# PressurePoints1X.net
KiCad netlist of a schematic drawn in EAGLE
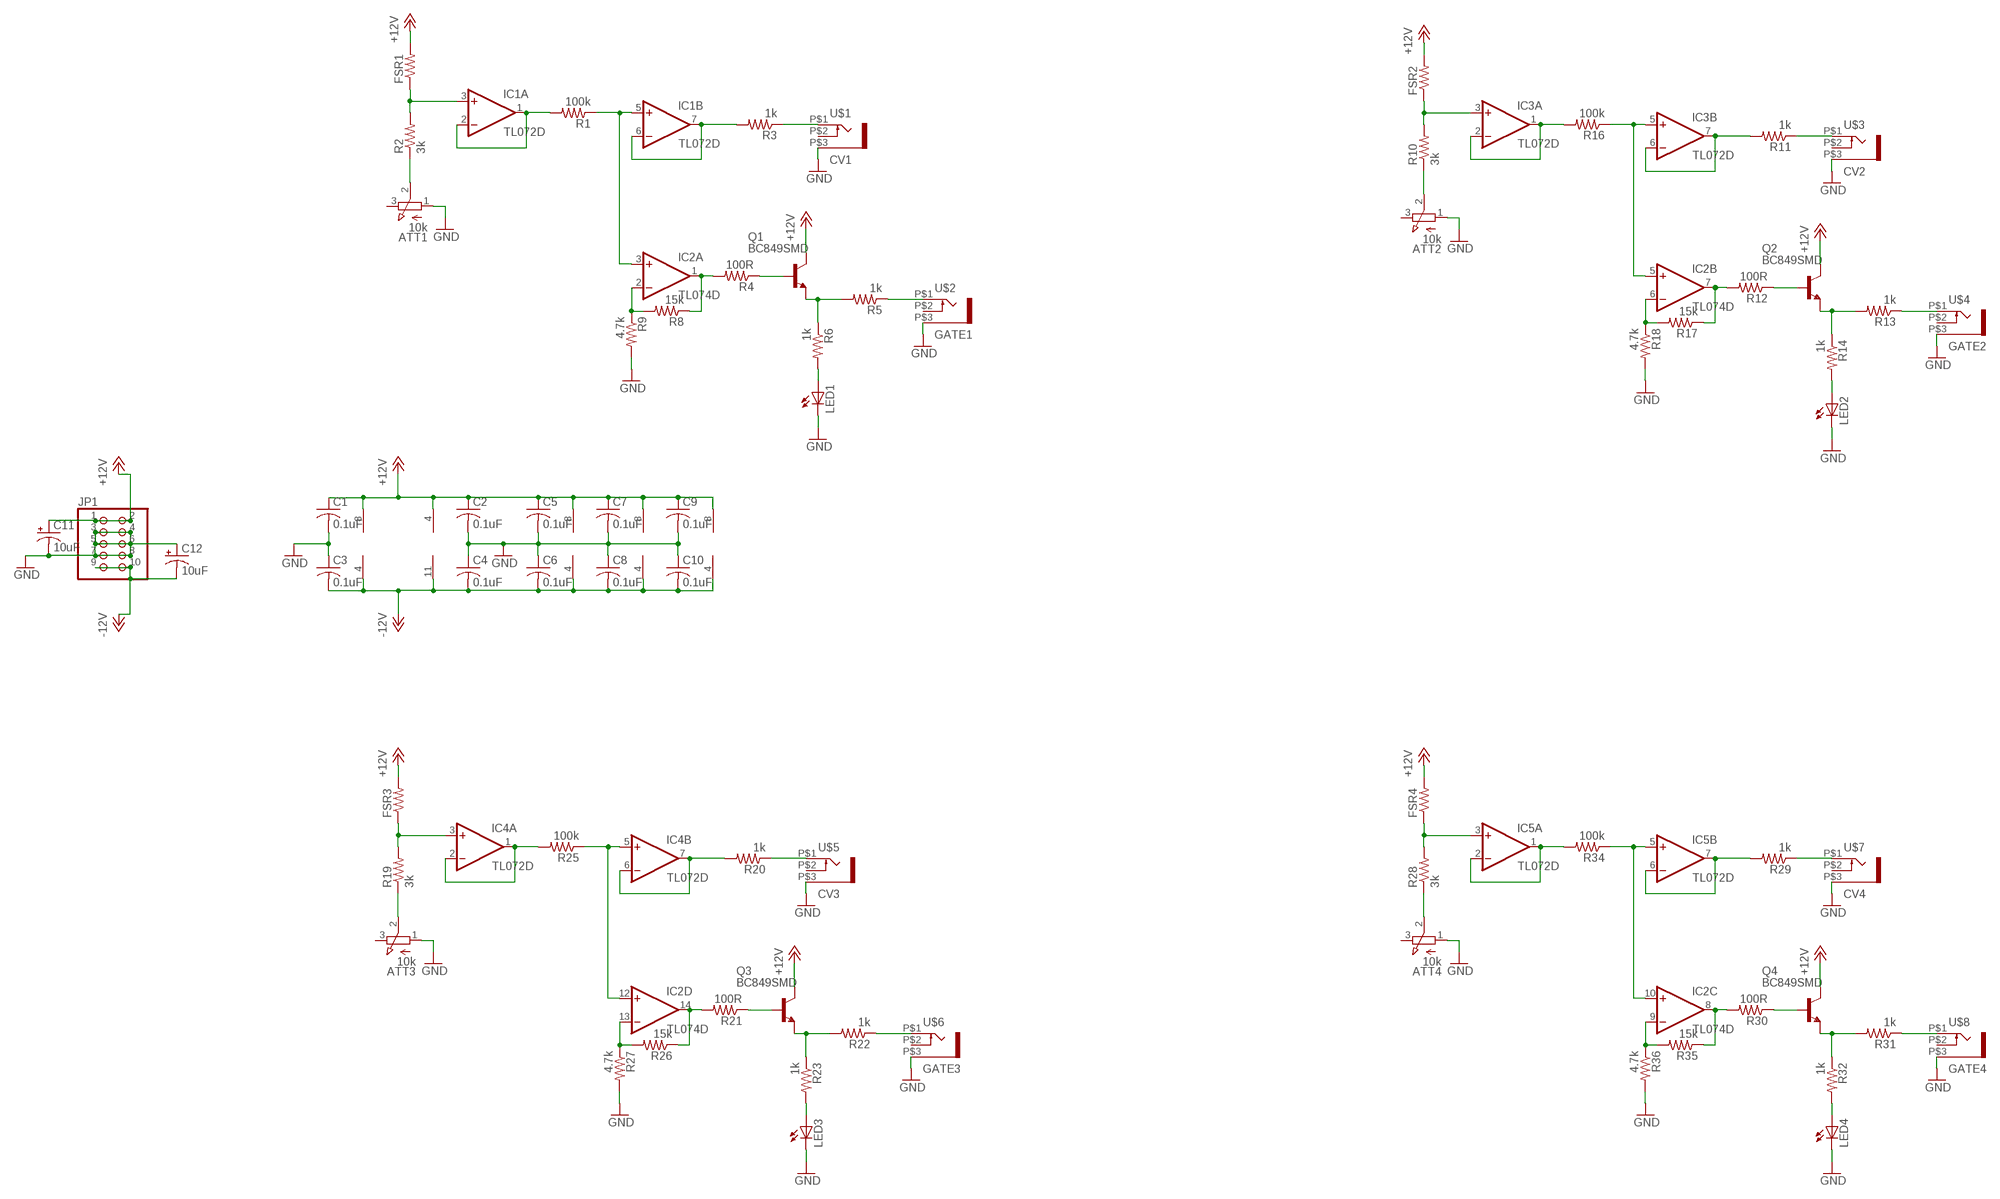
[diagram p0: schematic, sheet 1]

(export (version "E")
  (design (tool "Eeschema 10.0.6"))
  (components
    (comp (ref "ATT1")
      (value "10k")
      (footprint "eagle-import:EVUFXJ")
      (libsource (lib "eagle-import") (part "EVUF2J"))
    )
    (comp (ref "ATT2")
      (value "10k")
      (footprint "eagle-import:EVUFXJ")
      (libsource (lib "eagle-import") (part "EVUF2J"))
    )
    (comp (ref "ATT3")
      (value "10k")
      (footprint "eagle-import:EVUFXJ")
      (libsource (lib "eagle-import") (part "EVUF2J"))
    )
    (comp (ref "ATT4")
      (value "10k")
      (footprint "eagle-import:EVUFXJ")
      (libsource (lib "eagle-import") (part "EVUF2J"))
    )
    (comp (ref "C1")
      (value "0.1uF")
      (footprint "eagle-import:C0603")
      (libsource (lib "eagle-import") (part "C-USC0603"))
    )
    (comp (ref "C2")
      (value "0.1uF")
      (footprint "eagle-import:C0603")
      (libsource (lib "eagle-import") (part "C-USC0603"))
    )
    (comp (ref "C3")
      (value "0.1uF")
      (footprint "eagle-import:C0603")
      (libsource (lib "eagle-import") (part "C-USC0603"))
    )
    (comp (ref "C4")
      (value "0.1uF")
      (footprint "eagle-import:C0603")
      (libsource (lib "eagle-import") (part "C-USC0603"))
    )
    (comp (ref "C5")
      (value "0.1uF")
      (footprint "eagle-import:C0603")
      (libsource (lib "eagle-import") (part "C-USC0603"))
    )
    (comp (ref "C6")
      (value "0.1uF")
      (footprint "eagle-import:C0603")
      (libsource (lib "eagle-import") (part "C-USC0603"))
    )
    (comp (ref "C7")
      (value "0.1uF")
      (footprint "eagle-import:C0603")
      (libsource (lib "eagle-import") (part "C-USC0603"))
    )
    (comp (ref "C8")
      (value "0.1uF")
      (footprint "eagle-import:C0603")
      (libsource (lib "eagle-import") (part "C-USC0603"))
    )
    (comp (ref "C9")
      (value "0.1uF")
      (footprint "eagle-import:C0603")
      (libsource (lib "eagle-import") (part "C-USC0603"))
    )
    (comp (ref "C10")
      (value "0.1uF")
      (footprint "eagle-import:C0603")
      (libsource (lib "eagle-import") (part "C-USC0603"))
    )
    (comp (ref "C11")
      (value "10uF")
      (footprint "eagle-import:E2-5")
      (libsource (lib "eagle-import") (part "CPOL-USE2-5"))
    )
    (comp (ref "C12")
      (value "10uF")
      (footprint "eagle-import:E2-5")
      (libsource (lib "eagle-import") (part "CPOL-USE2-5"))
    )
    (comp (ref "FSR1")
      (value "R-US_0207/2V")
      (footprint "eagle-import:0207_2V")
      (libsource (lib "eagle-import") (part "R-US_0207/2V"))
    )
    (comp (ref "FSR2")
      (value "R-US_0207/2V")
      (footprint "eagle-import:0207_2V")
      (libsource (lib "eagle-import") (part "R-US_0207/2V"))
    )
    (comp (ref "FSR3")
      (value "R-US_0207/2V")
      (footprint "eagle-import:0207_2V")
      (libsource (lib "eagle-import") (part "R-US_0207/2V"))
    )
    (comp (ref "FSR4")
      (value "R-US_0207/2V")
      (footprint "eagle-import:0207_2V")
      (libsource (lib "eagle-import") (part "R-US_0207/2V"))
    )
    (comp (ref "IC1")
      (value "TL072D")
      (footprint "eagle-import:SO08")
      (libsource (lib "eagle-import") (part "TL072D"))
    )
    (comp (ref "IC2")
      (value "TL074D")
      (footprint "eagle-import:SO14")
      (libsource (lib "eagle-import") (part "TL074D"))
    )
    (comp (ref "IC3")
      (value "TL072D")
      (footprint "eagle-import:SO08")
      (libsource (lib "eagle-import") (part "TL072D"))
    )
    (comp (ref "IC4")
      (value "TL072D")
      (footprint "eagle-import:SO08")
      (libsource (lib "eagle-import") (part "TL072D"))
    )
    (comp (ref "IC5")
      (value "TL072D")
      (footprint "eagle-import:SO08")
      (libsource (lib "eagle-import") (part "TL072D"))
    )
    (comp (ref "JP1")
      (value "PINHD-2X5")
      (footprint "eagle-import:2X05")
      (libsource (lib "eagle-import") (part "PINHD-2X5"))
    )
    (comp (ref "LED1")
      (value "LED3MM")
      (footprint "eagle-import:LED3MM")
      (libsource (lib "eagle-import") (part "LED3MM"))
    )
    (comp (ref "LED2")
      (value "LED3MM")
      (footprint "eagle-import:LED3MM")
      (libsource (lib "eagle-import") (part "LED3MM"))
    )
    (comp (ref "LED3")
      (value "LED3MM")
      (footprint "eagle-import:LED3MM")
      (libsource (lib "eagle-import") (part "LED3MM"))
    )
    (comp (ref "LED4")
      (value "LED3MM")
      (footprint "eagle-import:LED3MM")
      (libsource (lib "eagle-import") (part "LED3MM"))
    )
    (comp (ref "Q1")
      (value "BC849SMD")
      (footprint "eagle-import:SOT23-BEC")
      (libsource (lib "eagle-import") (part "BC849SMD"))
    )
    (comp (ref "Q2")
      (value "BC849SMD")
      (footprint "eagle-import:SOT23-BEC")
      (libsource (lib "eagle-import") (part "BC849SMD"))
    )
    (comp (ref "Q3")
      (value "BC849SMD")
      (footprint "eagle-import:SOT23-BEC")
      (libsource (lib "eagle-import") (part "BC849SMD"))
    )
    (comp (ref "Q4")
      (value "BC849SMD")
      (footprint "eagle-import:SOT23-BEC")
      (libsource (lib "eagle-import") (part "BC849SMD"))
    )
    (comp (ref "R1")
      (value "100k")
      (footprint "eagle-import:R0603")
      (libsource (lib "eagle-import") (part "R-US_R0603"))
    )
    (comp (ref "R2")
      (value "3k")
      (footprint "eagle-import:R0603")
      (libsource (lib "eagle-import") (part "R-US_R0603"))
    )
    (comp (ref "R3")
      (value "1k")
      (footprint "eagle-import:R0603")
      (libsource (lib "eagle-import") (part "R-US_R0603"))
    )
    (comp (ref "R4")
      (value "100R")
      (footprint "eagle-import:R0603")
      (libsource (lib "eagle-import") (part "R-US_R0603"))
    )
    (comp (ref "R5")
      (value "1k")
      (footprint "eagle-import:R0603")
      (libsource (lib "eagle-import") (part "R-US_R0603"))
    )
    (comp (ref "R6")
      (value "1k")
      (footprint "eagle-import:R0603")
      (libsource (lib "eagle-import") (part "R-US_R0603"))
    )
    (comp (ref "R8")
      (value "15k")
      (footprint "eagle-import:R0603")
      (libsource (lib "eagle-import") (part "R-US_R0603"))
    )
    (comp (ref "R9")
      (value "4.7k")
      (footprint "eagle-import:R0603")
      (libsource (lib "eagle-import") (part "R-US_R0603"))
    )
    (comp (ref "R10")
      (value "3k")
      (footprint "eagle-import:R0603")
      (libsource (lib "eagle-import") (part "R-US_R0603"))
    )
    (comp (ref "R11")
      (value "1k")
      (footprint "eagle-import:R0603")
      (libsource (lib "eagle-import") (part "R-US_R0603"))
    )
    (comp (ref "R12")
      (value "100R")
      (footprint "eagle-import:R0603")
      (libsource (lib "eagle-import") (part "R-US_R0603"))
    )
    (comp (ref "R13")
      (value "1k")
      (footprint "eagle-import:R0603")
      (libsource (lib "eagle-import") (part "R-US_R0603"))
    )
    (comp (ref "R14")
      (value "1k")
      (footprint "eagle-import:R0603")
      (libsource (lib "eagle-import") (part "R-US_R0603"))
    )
    (comp (ref "R16")
      (value "100k")
      (footprint "eagle-import:R0603")
      (libsource (lib "eagle-import") (part "R-US_R0603"))
    )
    (comp (ref "R17")
      (value "15k")
      (footprint "eagle-import:R0603")
      (libsource (lib "eagle-import") (part "R-US_R0603"))
    )
    (comp (ref "R18")
      (value "4.7k")
      (footprint "eagle-import:R0603")
      (libsource (lib "eagle-import") (part "R-US_R0603"))
    )
    (comp (ref "R19")
      (value "3k")
      (footprint "eagle-import:R0603")
      (libsource (lib "eagle-import") (part "R-US_R0603"))
    )
    (comp (ref "R20")
      (value "1k")
      (footprint "eagle-import:R0603")
      (libsource (lib "eagle-import") (part "R-US_R0603"))
    )
    (comp (ref "R21")
      (value "100R")
      (footprint "eagle-import:R0603")
      (libsource (lib "eagle-import") (part "R-US_R0603"))
    )
    (comp (ref "R22")
      (value "1k")
      (footprint "eagle-import:R0603")
      (libsource (lib "eagle-import") (part "R-US_R0603"))
    )
    (comp (ref "R23")
      (value "1k")
      (footprint "eagle-import:R0603")
      (libsource (lib "eagle-import") (part "R-US_R0603"))
    )
    (comp (ref "R25")
      (value "100k")
      (footprint "eagle-import:R0603")
      (libsource (lib "eagle-import") (part "R-US_R0603"))
    )
    (comp (ref "R26")
      (value "15k")
      (footprint "eagle-import:R0603")
      (libsource (lib "eagle-import") (part "R-US_R0603"))
    )
    (comp (ref "R27")
      (value "4.7k")
      (footprint "eagle-import:R0603")
      (libsource (lib "eagle-import") (part "R-US_R0603"))
    )
    (comp (ref "R28")
      (value "3k")
      (footprint "eagle-import:R0603")
      (libsource (lib "eagle-import") (part "R-US_R0603"))
    )
    (comp (ref "R29")
      (value "1k")
      (footprint "eagle-import:R0603")
      (libsource (lib "eagle-import") (part "R-US_R0603"))
    )
    (comp (ref "R30")
      (value "100R")
      (footprint "eagle-import:R0603")
      (libsource (lib "eagle-import") (part "R-US_R0603"))
    )
    (comp (ref "R31")
      (value "1k")
      (footprint "eagle-import:R0603")
      (libsource (lib "eagle-import") (part "R-US_R0603"))
    )
    (comp (ref "R32")
      (value "1k")
      (footprint "eagle-import:R0603")
      (libsource (lib "eagle-import") (part "R-US_R0603"))
    )
    (comp (ref "R34")
      (value "100k")
      (footprint "eagle-import:R0603")
      (libsource (lib "eagle-import") (part "R-US_R0603"))
    )
    (comp (ref "R35")
      (value "15k")
      (footprint "eagle-import:R0603")
      (libsource (lib "eagle-import") (part "R-US_R0603"))
    )
    (comp (ref "R36")
      (value "4.7k")
      (footprint "eagle-import:R0603")
      (libsource (lib "eagle-import") (part "R-US_R0603"))
    )
    (comp (ref "U$1")
      (value "CV1")
      (footprint "eagle-import:WQP-PJ301M-12_JACK")
      (libsource (lib "eagle-import") (part "WQP-PJ301M-12_JACK"))
    )
    (comp (ref "U$2")
      (value "GATE1")
      (footprint "eagle-import:WQP-PJ301M-12_JACK")
      (libsource (lib "eagle-import") (part "WQP-PJ301M-12_JACK"))
    )
    (comp (ref "U$3")
      (value "CV2")
      (footprint "eagle-import:WQP-PJ301M-12_JACK")
      (libsource (lib "eagle-import") (part "WQP-PJ301M-12_JACK"))
    )
    (comp (ref "U$4")
      (value "GATE2")
      (footprint "eagle-import:WQP-PJ301M-12_JACK")
      (libsource (lib "eagle-import") (part "WQP-PJ301M-12_JACK"))
    )
    (comp (ref "U$5")
      (value "CV3")
      (footprint "eagle-import:WQP-PJ301M-12_JACK")
      (libsource (lib "eagle-import") (part "WQP-PJ301M-12_JACK"))
    )
    (comp (ref "U$6")
      (value "GATE3")
      (footprint "eagle-import:WQP-PJ301M-12_JACK")
      (libsource (lib "eagle-import") (part "WQP-PJ301M-12_JACK"))
    )
    (comp (ref "U$7")
      (value "CV4")
      (footprint "eagle-import:WQP-PJ301M-12_JACK")
      (libsource (lib "eagle-import") (part "WQP-PJ301M-12_JACK"))
    )
    (comp (ref "U$8")
      (value "GATE4")
      (footprint "eagle-import:WQP-PJ301M-12_JACK")
      (libsource (lib "eagle-import") (part "WQP-PJ301M-12_JACK"))
    )
  )
  (nets
    (net (code "1") (name "+12V") (class "Default")
      (node (ref "C1") (pin "1") (pinfunction "1_1") (pintype "passive"))
      (node (ref "C11") (pin "+") (pinfunction "+_+") (pintype "passive"))
      (node (ref "C2") (pin "1") (pinfunction "1_1") (pintype "passive"))
      (node (ref "C5") (pin "1") (pinfunction "1_1") (pintype "passive"))
      (node (ref "C7") (pin "1") (pinfunction "1_1") (pintype "passive"))
      (node (ref "C9") (pin "1") (pinfunction "1_1") (pintype "passive"))
      (node (ref "FSR1") (pin "2") (pinfunction "2_2") (pintype "passive"))
      (node (ref "FSR2") (pin "2") (pinfunction "2_2") (pintype "passive"))
      (node (ref "FSR3") (pin "2") (pinfunction "2_2") (pintype "passive"))
      (node (ref "FSR4") (pin "2") (pinfunction "2_2") (pintype "passive"))
      (node (ref "IC1") (pin "8") (pinfunction "V+_8") (pintype "power_in"))
      (node (ref "IC2") (pin "4") (pinfunction "V+_4") (pintype "power_in"))
      (node (ref "IC3") (pin "8") (pinfunction "V+_8") (pintype "power_in"))
      (node (ref "IC4") (pin "8") (pinfunction "V+_8") (pintype "power_in"))
      (node (ref "IC5") (pin "8") (pinfunction "V+_8") (pintype "power_in"))
      (node (ref "JP1") (pin "1") (pinfunction "1_1") (pintype "passive"))
      (node (ref "JP1") (pin "2") (pinfunction "2_2") (pintype "passive"))
      (node (ref "Q1") (pin "C") (pinfunction "C_C") (pintype "passive"))
      (node (ref "Q2") (pin "C") (pinfunction "C_C") (pintype "passive"))
      (node (ref "Q3") (pin "C") (pinfunction "C_C") (pintype "passive"))
      (node (ref "Q4") (pin "C") (pinfunction "C_C") (pintype "passive"))
    )
    (net (code "2") (name "-12V") (class "Default")
      (node (ref "C10") (pin "2") (pinfunction "2_2") (pintype "passive"))
      (node (ref "C12") (pin "-") (pinfunction "-_-") (pintype "passive"))
      (node (ref "C3") (pin "2") (pinfunction "2_2") (pintype "passive"))
      (node (ref "C4") (pin "2") (pinfunction "2_2") (pintype "passive"))
      (node (ref "C6") (pin "2") (pinfunction "2_2") (pintype "passive"))
      (node (ref "C8") (pin "2") (pinfunction "2_2") (pintype "passive"))
      (node (ref "IC1") (pin "4") (pinfunction "V-_4") (pintype "power_in"))
      (node (ref "IC2") (pin "11") (pinfunction "V-_11") (pintype "power_in"))
      (node (ref "IC3") (pin "4") (pinfunction "V-_4") (pintype "power_in"))
      (node (ref "IC4") (pin "4") (pinfunction "V-_4") (pintype "power_in"))
      (node (ref "IC5") (pin "4") (pinfunction "V-_4") (pintype "power_in"))
      (node (ref "JP1") (pin "10") (pinfunction "10_10") (pintype "passive"))
      (node (ref "JP1") (pin "9") (pinfunction "9_9") (pintype "passive"))
    )
    (net (code "3") (name "GND") (class "Default")
      (node (ref "ATT1") (pin "1") (pinfunction "A_1") (pintype "passive"))
      (node (ref "ATT2") (pin "1") (pinfunction "A_1") (pintype "passive"))
      (node (ref "ATT3") (pin "1") (pinfunction "A_1") (pintype "passive"))
      (node (ref "ATT4") (pin "1") (pinfunction "A_1") (pintype "passive"))
      (node (ref "C1") (pin "2") (pinfunction "2_2") (pintype "passive"))
      (node (ref "C10") (pin "1") (pinfunction "1_1") (pintype "passive"))
      (node (ref "C11") (pin "-") (pinfunction "-_-") (pintype "passive"))
      (node (ref "C12") (pin "+") (pinfunction "+_+") (pintype "passive"))
      (node (ref "C2") (pin "2") (pinfunction "2_2") (pintype "passive"))
      (node (ref "C3") (pin "1") (pinfunction "1_1") (pintype "passive"))
      (node (ref "C4") (pin "1") (pinfunction "1_1") (pintype "passive"))
      (node (ref "C5") (pin "2") (pinfunction "2_2") (pintype "passive"))
      (node (ref "C6") (pin "1") (pinfunction "1_1") (pintype "passive"))
      (node (ref "C7") (pin "2") (pinfunction "2_2") (pintype "passive"))
      (node (ref "C8") (pin "1") (pinfunction "1_1") (pintype "passive"))
      (node (ref "C9") (pin "2") (pinfunction "2_2") (pintype "passive"))
      (node (ref "JP1") (pin "3") (pinfunction "3_3") (pintype "passive"))
      (node (ref "JP1") (pin "4") (pinfunction "4_4") (pintype "passive"))
      (node (ref "JP1") (pin "5") (pinfunction "5_5") (pintype "passive"))
      (node (ref "JP1") (pin "6") (pinfunction "6_6") (pintype "passive"))
      (node (ref "JP1") (pin "7") (pinfunction "7_7") (pintype "passive"))
      (node (ref "JP1") (pin "8") (pinfunction "8_8") (pintype "passive"))
      (node (ref "LED1") (pin "K") (pinfunction "C_K") (pintype "passive"))
      (node (ref "LED2") (pin "K") (pinfunction "C_K") (pintype "passive"))
      (node (ref "LED3") (pin "K") (pinfunction "C_K") (pintype "passive"))
      (node (ref "LED4") (pin "K") (pinfunction "C_K") (pintype "passive"))
      (node (ref "R18") (pin "2") (pinfunction "2_2") (pintype "passive"))
      (node (ref "R27") (pin "2") (pinfunction "2_2") (pintype "passive"))
      (node (ref "R36") (pin "2") (pinfunction "2_2") (pintype "passive"))
      (node (ref "R9") (pin "2") (pinfunction "2_2") (pintype "passive"))
      (node (ref "U$1") (pin "P$3") (pinfunction "1_P$3") (pintype "passive"))
      (node (ref "U$2") (pin "P$3") (pinfunction "1_P$3") (pintype "passive"))
      (node (ref "U$3") (pin "P$3") (pinfunction "1_P$3") (pintype "passive"))
      (node (ref "U$4") (pin "P$3") (pinfunction "1_P$3") (pintype "passive"))
      (node (ref "U$5") (pin "P$3") (pinfunction "1_P$3") (pintype "passive"))
      (node (ref "U$6") (pin "P$3") (pinfunction "1_P$3") (pintype "passive"))
      (node (ref "U$7") (pin "P$3") (pinfunction "1_P$3") (pintype "passive"))
      (node (ref "U$8") (pin "P$3") (pinfunction "1_P$3") (pintype "passive"))
    )
    (net (code "4") (name "Net-(ATT1-S)") (class "Default")
      (node (ref "ATT1") (pin "2") (pinfunction "S_2") (pintype "passive"))
      (node (ref "R2") (pin "1") (pinfunction "1_1") (pintype "passive"))
    )
    (net (code "5") (name "Net-(ATT2-S)") (class "Default")
      (node (ref "ATT2") (pin "2") (pinfunction "S_2") (pintype "passive"))
      (node (ref "R10") (pin "1") (pinfunction "1_1") (pintype "passive"))
    )
    (net (code "6") (name "Net-(ATT3-S)") (class "Default")
      (node (ref "ATT3") (pin "2") (pinfunction "S_2") (pintype "passive"))
      (node (ref "R19") (pin "1") (pinfunction "1_1") (pintype "passive"))
    )
    (net (code "7") (name "Net-(ATT4-S)") (class "Default")
      (node (ref "ATT4") (pin "2") (pinfunction "S_2") (pintype "passive"))
      (node (ref "R28") (pin "1") (pinfunction "1_1") (pintype "passive"))
    )
    (net (code "8") (name "Net-(IC1A-+IN)") (class "Default")
      (node (ref "FSR1") (pin "1") (pinfunction "1_1") (pintype "passive"))
      (node (ref "IC1") (pin "3") (pinfunction "+IN_3") (pintype "input"))
      (node (ref "R2") (pin "2") (pinfunction "2_2") (pintype "passive"))
    )
    (net (code "9") (name "Net-(IC1A--IN)") (class "Default")
      (node (ref "IC1") (pin "1") (pinfunction "OUT_1") (pintype "output"))
      (node (ref "IC1") (pin "2") (pinfunction "-IN_2") (pintype "input"))
      (node (ref "R1") (pin "2") (pinfunction "2_2") (pintype "passive"))
    )
    (net (code "10") (name "Net-(IC1B-+IN)") (class "Default")
      (node (ref "IC1") (pin "5") (pinfunction "+IN_5") (pintype "input"))
      (node (ref "IC2") (pin "3") (pinfunction "+IN_3") (pintype "input"))
      (node (ref "R1") (pin "1") (pinfunction "1_1") (pintype "passive"))
    )
    (net (code "11") (name "Net-(IC1B--IN)") (class "Default")
      (node (ref "IC1") (pin "6") (pinfunction "-IN_6") (pintype "input"))
      (node (ref "IC1") (pin "7") (pinfunction "OUT_7") (pintype "output"))
      (node (ref "R3") (pin "2") (pinfunction "2_2") (pintype "passive"))
    )
    (net (code "12") (name "Net-(IC2A--IN)") (class "Default")
      (node (ref "IC2") (pin "2") (pinfunction "-IN_2") (pintype "input"))
      (node (ref "R8") (pin "2") (pinfunction "2_2") (pintype "passive"))
      (node (ref "R9") (pin "1") (pinfunction "1_1") (pintype "passive"))
    )
    (net (code "13") (name "Net-(IC2A-OUT)") (class "Default")
      (node (ref "IC2") (pin "1") (pinfunction "OUT_1") (pintype "output"))
      (node (ref "R4") (pin "2") (pinfunction "2_2") (pintype "passive"))
      (node (ref "R8") (pin "1") (pinfunction "1_1") (pintype "passive"))
    )
    (net (code "14") (name "Net-(IC2B-+IN)") (class "Default")
      (node (ref "IC2") (pin "5") (pinfunction "+IN_5") (pintype "input"))
      (node (ref "IC3") (pin "5") (pinfunction "+IN_5") (pintype "input"))
      (node (ref "R16") (pin "1") (pinfunction "1_1") (pintype "passive"))
    )
    (net (code "15") (name "Net-(IC2B--IN)") (class "Default")
      (node (ref "IC2") (pin "6") (pinfunction "-IN_6") (pintype "input"))
      (node (ref "R17") (pin "2") (pinfunction "2_2") (pintype "passive"))
      (node (ref "R18") (pin "1") (pinfunction "1_1") (pintype "passive"))
    )
    (net (code "16") (name "Net-(IC2B-OUT)") (class "Default")
      (node (ref "IC2") (pin "7") (pinfunction "OUT_7") (pintype "output"))
      (node (ref "R12") (pin "2") (pinfunction "2_2") (pintype "passive"))
      (node (ref "R17") (pin "1") (pinfunction "1_1") (pintype "passive"))
    )
    (net (code "17") (name "Net-(IC2C-+IN)") (class "Default")
      (node (ref "IC2") (pin "10") (pinfunction "+IN_10") (pintype "input"))
      (node (ref "IC5") (pin "5") (pinfunction "+IN_5") (pintype "input"))
      (node (ref "R34") (pin "1") (pinfunction "1_1") (pintype "passive"))
    )
    (net (code "18") (name "Net-(IC2C--IN)") (class "Default")
      (node (ref "IC2") (pin "9") (pinfunction "-IN_9") (pintype "input"))
      (node (ref "R35") (pin "2") (pinfunction "2_2") (pintype "passive"))
      (node (ref "R36") (pin "1") (pinfunction "1_1") (pintype "passive"))
    )
    (net (code "19") (name "Net-(IC2C-OUT)") (class "Default")
      (node (ref "IC2") (pin "8") (pinfunction "OUT_8") (pintype "output"))
      (node (ref "R30") (pin "2") (pinfunction "2_2") (pintype "passive"))
      (node (ref "R35") (pin "1") (pinfunction "1_1") (pintype "passive"))
    )
    (net (code "20") (name "Net-(IC2D-+IN)") (class "Default")
      (node (ref "IC2") (pin "12") (pinfunction "+IN_12") (pintype "input"))
      (node (ref "IC4") (pin "5") (pinfunction "+IN_5") (pintype "input"))
      (node (ref "R25") (pin "1") (pinfunction "1_1") (pintype "passive"))
    )
    (net (code "21") (name "Net-(IC2D--IN)") (class "Default")
      (node (ref "IC2") (pin "13") (pinfunction "-IN_13") (pintype "input"))
      (node (ref "R26") (pin "2") (pinfunction "2_2") (pintype "passive"))
      (node (ref "R27") (pin "1") (pinfunction "1_1") (pintype "passive"))
    )
    (net (code "22") (name "Net-(IC2D-OUT)") (class "Default")
      (node (ref "IC2") (pin "14") (pinfunction "OUT_14") (pintype "output"))
      (node (ref "R21") (pin "2") (pinfunction "2_2") (pintype "passive"))
      (node (ref "R26") (pin "1") (pinfunction "1_1") (pintype "passive"))
    )
    (net (code "23") (name "Net-(IC3A-+IN)") (class "Default")
      (node (ref "FSR2") (pin "1") (pinfunction "1_1") (pintype "passive"))
      (node (ref "IC3") (pin "3") (pinfunction "+IN_3") (pintype "input"))
      (node (ref "R10") (pin "2") (pinfunction "2_2") (pintype "passive"))
    )
    (net (code "24") (name "Net-(IC3A--IN)") (class "Default")
      (node (ref "IC3") (pin "1") (pinfunction "OUT_1") (pintype "output"))
      (node (ref "IC3") (pin "2") (pinfunction "-IN_2") (pintype "input"))
      (node (ref "R16") (pin "2") (pinfunction "2_2") (pintype "passive"))
    )
    (net (code "25") (name "Net-(IC3B--IN)") (class "Default")
      (node (ref "IC3") (pin "6") (pinfunction "-IN_6") (pintype "input"))
      (node (ref "IC3") (pin "7") (pinfunction "OUT_7") (pintype "output"))
      (node (ref "R11") (pin "2") (pinfunction "2_2") (pintype "passive"))
    )
    (net (code "26") (name "Net-(IC4A-+IN)") (class "Default")
      (node (ref "FSR3") (pin "1") (pinfunction "1_1") (pintype "passive"))
      (node (ref "IC4") (pin "3") (pinfunction "+IN_3") (pintype "input"))
      (node (ref "R19") (pin "2") (pinfunction "2_2") (pintype "passive"))
    )
    (net (code "27") (name "Net-(IC4A--IN)") (class "Default")
      (node (ref "IC4") (pin "1") (pinfunction "OUT_1") (pintype "output"))
      (node (ref "IC4") (pin "2") (pinfunction "-IN_2") (pintype "input"))
      (node (ref "R25") (pin "2") (pinfunction "2_2") (pintype "passive"))
    )
    (net (code "28") (name "Net-(IC4B--IN)") (class "Default")
      (node (ref "IC4") (pin "6") (pinfunction "-IN_6") (pintype "input"))
      (node (ref "IC4") (pin "7") (pinfunction "OUT_7") (pintype "output"))
      (node (ref "R20") (pin "2") (pinfunction "2_2") (pintype "passive"))
    )
    (net (code "29") (name "Net-(IC5A-+IN)") (class "Default")
      (node (ref "FSR4") (pin "1") (pinfunction "1_1") (pintype "passive"))
      (node (ref "IC5") (pin "3") (pinfunction "+IN_3") (pintype "input"))
      (node (ref "R28") (pin "2") (pinfunction "2_2") (pintype "passive"))
    )
    (net (code "30") (name "Net-(IC5A--IN)") (class "Default")
      (node (ref "IC5") (pin "1") (pinfunction "OUT_1") (pintype "output"))
      (node (ref "IC5") (pin "2") (pinfunction "-IN_2") (pintype "input"))
      (node (ref "R34") (pin "2") (pinfunction "2_2") (pintype "passive"))
    )
    (net (code "31") (name "Net-(IC5B--IN)") (class "Default")
      (node (ref "IC5") (pin "6") (pinfunction "-IN_6") (pintype "input"))
      (node (ref "IC5") (pin "7") (pinfunction "OUT_7") (pintype "output"))
      (node (ref "R29") (pin "2") (pinfunction "2_2") (pintype "passive"))
    )
    (net (code "32") (name "Net-(LED1-PadA)") (class "Default")
      (node (ref "LED1") (pin "A") (pinfunction "A_A") (pintype "passive"))
      (node (ref "R6") (pin "2") (pinfunction "2_2") (pintype "passive"))
    )
    (net (code "33") (name "Net-(LED2-PadA)") (class "Default")
      (node (ref "LED2") (pin "A") (pinfunction "A_A") (pintype "passive"))
      (node (ref "R14") (pin "2") (pinfunction "2_2") (pintype "passive"))
    )
    (net (code "34") (name "Net-(LED3-PadA)") (class "Default")
      (node (ref "LED3") (pin "A") (pinfunction "A_A") (pintype "passive"))
      (node (ref "R23") (pin "2") (pinfunction "2_2") (pintype "passive"))
    )
    (net (code "35") (name "Net-(LED4-PadA)") (class "Default")
      (node (ref "LED4") (pin "A") (pinfunction "A_A") (pintype "passive"))
      (node (ref "R32") (pin "2") (pinfunction "2_2") (pintype "passive"))
    )
    (net (code "36") (name "Net-(Q1-PadB)") (class "Default")
      (node (ref "Q1") (pin "B") (pinfunction "B_B") (pintype "passive"))
      (node (ref "R4") (pin "1") (pinfunction "1_1") (pintype "passive"))
    )
    (net (code "37") (name "Net-(Q1-PadE)") (class "Default")
      (node (ref "Q1") (pin "E") (pinfunction "E_E") (pintype "passive"))
      (node (ref "R5") (pin "2") (pinfunction "2_2") (pintype "passive"))
      (node (ref "R6") (pin "1") (pinfunction "1_1") (pintype "passive"))
    )
    (net (code "38") (name "Net-(Q2-PadB)") (class "Default")
      (node (ref "Q2") (pin "B") (pinfunction "B_B") (pintype "passive"))
      (node (ref "R12") (pin "1") (pinfunction "1_1") (pintype "passive"))
    )
    (net (code "39") (name "Net-(Q2-PadE)") (class "Default")
      (node (ref "Q2") (pin "E") (pinfunction "E_E") (pintype "passive"))
      (node (ref "R13") (pin "2") (pinfunction "2_2") (pintype "passive"))
      (node (ref "R14") (pin "1") (pinfunction "1_1") (pintype "passive"))
    )
    (net (code "40") (name "Net-(Q3-PadB)") (class "Default")
      (node (ref "Q3") (pin "B") (pinfunction "B_B") (pintype "passive"))
      (node (ref "R21") (pin "1") (pinfunction "1_1") (pintype "passive"))
    )
    (net (code "41") (name "Net-(Q3-PadE)") (class "Default")
      (node (ref "Q3") (pin "E") (pinfunction "E_E") (pintype "passive"))
      (node (ref "R22") (pin "2") (pinfunction "2_2") (pintype "passive"))
      (node (ref "R23") (pin "1") (pinfunction "1_1") (pintype "passive"))
    )
    (net (code "42") (name "Net-(Q4-PadB)") (class "Default")
      (node (ref "Q4") (pin "B") (pinfunction "B_B") (pintype "passive"))
      (node (ref "R30") (pin "1") (pinfunction "1_1") (pintype "passive"))
    )
    (net (code "43") (name "Net-(Q4-PadE)") (class "Default")
      (node (ref "Q4") (pin "E") (pinfunction "E_E") (pintype "passive"))
      (node (ref "R31") (pin "2") (pinfunction "2_2") (pintype "passive"))
      (node (ref "R32") (pin "1") (pinfunction "1_1") (pintype "passive"))
    )
    (net (code "44") (name "Net-(U$1-2)") (class "Default")
      (node (ref "R3") (pin "1") (pinfunction "1_1") (pintype "passive"))
      (node (ref "U$1") (pin "P$1") (pinfunction "2_P$1") (pintype "passive"))
    )
    (net (code "45") (name "Net-(U$2-2)") (class "Default")
      (node (ref "R5") (pin "1") (pinfunction "1_1") (pintype "passive"))
      (node (ref "U$2") (pin "P$1") (pinfunction "2_P$1") (pintype "passive"))
    )
    (net (code "46") (name "Net-(U$3-2)") (class "Default")
      (node (ref "R11") (pin "1") (pinfunction "1_1") (pintype "passive"))
      (node (ref "U$3") (pin "P$1") (pinfunction "2_P$1") (pintype "passive"))
    )
    (net (code "47") (name "Net-(U$4-2)") (class "Default")
      (node (ref "R13") (pin "1") (pinfunction "1_1") (pintype "passive"))
      (node (ref "U$4") (pin "P$1") (pinfunction "2_P$1") (pintype "passive"))
    )
    (net (code "48") (name "Net-(U$5-2)") (class "Default")
      (node (ref "R20") (pin "1") (pinfunction "1_1") (pintype "passive"))
      (node (ref "U$5") (pin "P$1") (pinfunction "2_P$1") (pintype "passive"))
    )
    (net (code "49") (name "Net-(U$6-2)") (class "Default")
      (node (ref "R22") (pin "1") (pinfunction "1_1") (pintype "passive"))
      (node (ref "U$6") (pin "P$1") (pinfunction "2_P$1") (pintype "passive"))
    )
    (net (code "50") (name "Net-(U$7-2)") (class "Default")
      (node (ref "R29") (pin "1") (pinfunction "1_1") (pintype "passive"))
      (node (ref "U$7") (pin "P$1") (pinfunction "2_P$1") (pintype "passive"))
    )
    (net (code "51") (name "Net-(U$8-2)") (class "Default")
      (node (ref "R31") (pin "1") (pinfunction "1_1") (pintype "passive"))
      (node (ref "U$8") (pin "P$1") (pinfunction "2_P$1") (pintype "passive"))
    )
    (net (code "52") (name "unconnected-(ATT1-E-Pad3)") (class "Default")
      (node (ref "ATT1") (pin "3") (pinfunction "E_3") (pintype "passive"))
    )
    (net (code "53") (name "unconnected-(ATT2-E-Pad3)") (class "Default")
      (node (ref "ATT2") (pin "3") (pinfunction "E_3") (pintype "passive"))
    )
    (net (code "54") (name "unconnected-(ATT3-E-Pad3)") (class "Default")
      (node (ref "ATT3") (pin "3") (pinfunction "E_3") (pintype "passive"))
    )
    (net (code "55") (name "unconnected-(ATT4-E-Pad3)") (class "Default")
      (node (ref "ATT4") (pin "3") (pinfunction "E_3") (pintype "passive"))
    )
    (net (code "56") (name "unconnected-(U$1-3-PadP$2)") (class "Default")
      (node (ref "U$1") (pin "P$2") (pinfunction "3_P$2") (pintype "passive"))
    )
    (net (code "57") (name "unconnected-(U$2-3-PadP$2)") (class "Default")
      (node (ref "U$2") (pin "P$2") (pinfunction "3_P$2") (pintype "passive"))
    )
    (net (code "58") (name "unconnected-(U$3-3-PadP$2)") (class "Default")
      (node (ref "U$3") (pin "P$2") (pinfunction "3_P$2") (pintype "passive"))
    )
    (net (code "59") (name "unconnected-(U$4-3-PadP$2)") (class "Default")
      (node (ref "U$4") (pin "P$2") (pinfunction "3_P$2") (pintype "passive"))
    )
    (net (code "60") (name "unconnected-(U$5-3-PadP$2)") (class "Default")
      (node (ref "U$5") (pin "P$2") (pinfunction "3_P$2") (pintype "passive"))
    )
    (net (code "61") (name "unconnected-(U$6-3-PadP$2)") (class "Default")
      (node (ref "U$6") (pin "P$2") (pinfunction "3_P$2") (pintype "passive"))
    )
    (net (code "62") (name "unconnected-(U$7-3-PadP$2)") (class "Default")
      (node (ref "U$7") (pin "P$2") (pinfunction "3_P$2") (pintype "passive"))
    )
    (net (code "63") (name "unconnected-(U$8-3-PadP$2)") (class "Default")
      (node (ref "U$8") (pin "P$2") (pinfunction "3_P$2") (pintype "passive"))
    )
  )
)
